# INOUT.net
KiCad netlist of a schematic drawn in Altium Designer
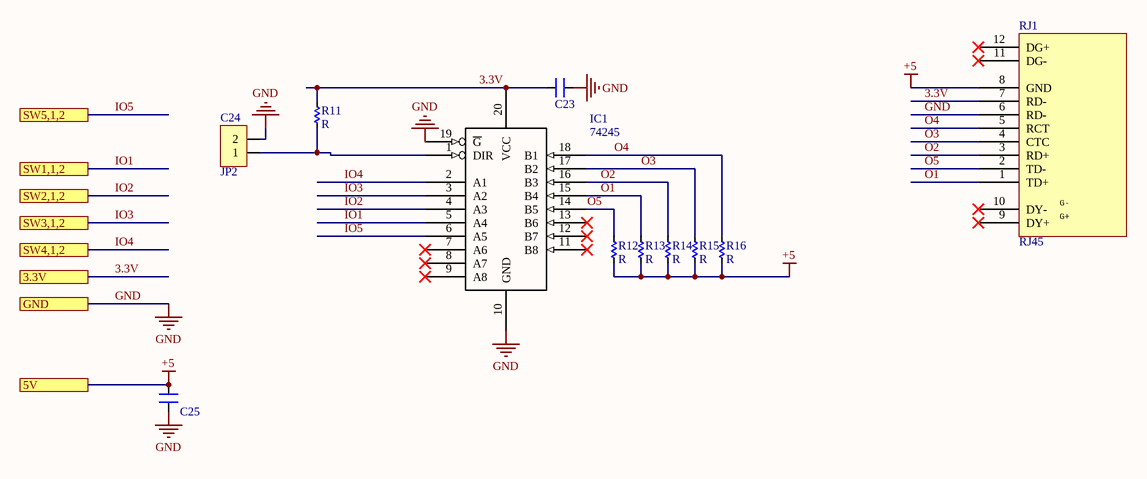
[diagram p0: INOUT.SchDoc]

(export (version "E")
  (design (tool "Eeschema 10.0.6"))
  (components
    (comp (ref "C23") (value "CN") (footprint "CN-SMD-0603_big") (libsource (lib "nhan") (part "CN")))
    (comp (ref "C24")
      (value "JP2")
      (footprint "JP2-CLOSED")
      (description "WR-PHD 2.54 mm Angled Socket Header")
      (fields
        (field (name "MANUFACTURER") "Würth Elektronik eiSos GmbH")
        (field (name "PARTNO") "613002143121")
        (field (name "CREATED BY") "Karrer Zheng")
      )
      (libsource (lib "nhan") (part "JP2"))
    )
    (comp (ref "C25") (value "CN") (footprint "CN-SMD-0603_big") (libsource (lib "nhan") (part "CN")))
    (comp (ref "IC1")
      (value "74245")
      (footprint "SO20")
      (description "Octal bus tranceiver; 3-state")
      (fields (field (name "COPYRIGHT BY") "VanDungEvn@gmail.com"))
      (libsource (lib "BanLinhKien") (part "74245"))
    )
    (comp (ref "R11") (value "R") (footprint "RES-SMD-0603_BIG") (libsource (lib "nhan") (part "R")))
    (comp (ref "R12") (value "R") (footprint "RES-SMD-0603_BIG") (libsource (lib "nhan") (part "R")))
    (comp (ref "R13") (value "R") (footprint "RES-SMD-0603_BIG") (libsource (lib "nhan") (part "R")))
    (comp (ref "R14") (value "R") (footprint "RES-SMD-0603_BIG") (libsource (lib "nhan") (part "R")))
    (comp (ref "R15") (value "R") (footprint "RES-SMD-0603_BIG") (libsource (lib "nhan") (part "R")))
    (comp (ref "R16") (value "R") (footprint "RES-SMD-0603_BIG") (libsource (lib "nhan") (part "R")))
    (comp (ref "RJ1") (value "RJ45") (footprint "RJ45-Dung") (libsource (lib "nhan") (part "CON JR45")))
  )
  (nets
    (net (code "1") (name "+5") (class "Default")
      (node (ref "C25") (pin "2") (pinfunction "2_2") (pintype "passive"))
      (node (ref "R12") (pin "2") (pinfunction "2_2") (pintype "passive"))
      (node (ref "R13") (pin "2") (pinfunction "2_2") (pintype "passive"))
      (node (ref "R14") (pin "2") (pinfunction "2_2") (pintype "passive"))
      (node (ref "R15") (pin "2") (pinfunction "2_2") (pintype "passive"))
      (node (ref "R16") (pin "2") (pinfunction "2_2") (pintype "passive"))
      (node (ref "RJ1") (pin "8") (pinfunction "GND_8") (pintype "power_in"))
    )
    (net (code "2") (name "/3.3V") (class "Default")
      (node (ref "C23") (pin "1") (pinfunction "1_1") (pintype "passive"))
      (node (ref "IC1") (pin "20") (pinfunction "VCC_20") (pintype "power_in"))
      (node (ref "R11") (pin "1") (pinfunction "1_1") (pintype "passive"))
      (node (ref "RJ1") (pin "7") (pinfunction "RD-_7") (pintype "passive"))
    )
    (net (code "3") (name "/IO1") (class "Default")
      (node (ref "IC1") (pin "5") (pinfunction "A4_5") (pintype "tri_state"))
    )
    (net (code "4") (name "/IO2") (class "Default")
      (node (ref "IC1") (pin "4") (pinfunction "A3_4") (pintype "tri_state"))
    )
    (net (code "5") (name "/IO3") (class "Default")
      (node (ref "IC1") (pin "3") (pinfunction "A2_3") (pintype "tri_state"))
    )
    (net (code "6") (name "/IO4") (class "Default")
      (node (ref "IC1") (pin "2") (pinfunction "A1_2") (pintype "tri_state"))
    )
    (net (code "7") (name "/IO5") (class "Default")
      (node (ref "IC1") (pin "6") (pinfunction "A5_6") (pintype "tri_state"))
    )
    (net (code "8") (name "/O1") (class "Default")
      (node (ref "IC1") (pin "15") (pinfunction "B4_15") (pintype "input"))
      (node (ref "R13") (pin "1") (pinfunction "1_1") (pintype "passive"))
      (node (ref "RJ1") (pin "1") (pinfunction "TD+_1") (pintype "passive"))
    )
    (net (code "9") (name "/O2") (class "Default")
      (node (ref "IC1") (pin "16") (pinfunction "B3_16") (pintype "input"))
      (node (ref "R14") (pin "1") (pinfunction "1_1") (pintype "passive"))
      (node (ref "RJ1") (pin "3") (pinfunction "RD+_3") (pintype "passive"))
    )
    (net (code "10") (name "/O3") (class "Default")
      (node (ref "IC1") (pin "17") (pinfunction "B2_17") (pintype "input"))
      (node (ref "R15") (pin "1") (pinfunction "1_1") (pintype "passive"))
      (node (ref "RJ1") (pin "4") (pinfunction "CTC_4") (pintype "passive"))
    )
    (net (code "11") (name "/O4") (class "Default")
      (node (ref "IC1") (pin "18") (pinfunction "B1_18") (pintype "input"))
      (node (ref "R16") (pin "1") (pinfunction "1_1") (pintype "passive"))
      (node (ref "RJ1") (pin "5") (pinfunction "RCT_5") (pintype "passive"))
    )
    (net (code "12") (name "/O5") (class "Default")
      (node (ref "IC1") (pin "14") (pinfunction "B5_14") (pintype "input"))
      (node (ref "R12") (pin "1") (pinfunction "1_1") (pintype "passive"))
      (node (ref "RJ1") (pin "2") (pinfunction "TD-_2") (pintype "passive"))
    )
    (net (code "13") (name "GND") (class "Default")
      (node (ref "C23") (pin "2") (pinfunction "2_2") (pintype "passive"))
      (node (ref "C24") (pin "2") (pinfunction "2_2") (pintype "passive"))
      (node (ref "C25") (pin "1") (pinfunction "1_1") (pintype "passive"))
      (node (ref "IC1") (pin "10") (pinfunction "GND_10") (pintype "power_in"))
      (node (ref "IC1") (pin "19") (pinfunction "~{G}_19") (pintype "input"))
      (node (ref "RJ1") (pin "6") (pinfunction "RD-_6") (pintype "passive"))
    )
    (net (code "14") (name "Net-(IC1-DIR)") (class "Default")
      (node (ref "C24") (pin "1") (pinfunction "1_1") (pintype "passive"))
      (node (ref "IC1") (pin "1") (pinfunction "DIR_1") (pintype "input"))
      (node (ref "R11") (pin "2") (pinfunction "2_2") (pintype "passive"))
    )
    (net (code "15") (name "unconnected-(IC1-A6-Pad7)") (class "Default")
      (node (ref "IC1") (pin "7") (pinfunction "A6_7") (pintype "tri_state+no_connect"))
    )
    (net (code "16") (name "unconnected-(IC1-A7-Pad8)") (class "Default")
      (node (ref "IC1") (pin "8") (pinfunction "A7_8") (pintype "tri_state+no_connect"))
    )
    (net (code "17") (name "unconnected-(IC1-A8-Pad9)") (class "Default")
      (node (ref "IC1") (pin "9") (pinfunction "A8_9") (pintype "tri_state+no_connect"))
    )
    (net (code "18") (name "unconnected-(IC1-B6-Pad13)") (class "Default")
      (node (ref "IC1") (pin "13") (pinfunction "B6_13") (pintype "input+no_connect"))
    )
    (net (code "19") (name "unconnected-(IC1-B7-Pad12)") (class "Default")
      (node (ref "IC1") (pin "12") (pinfunction "B7_12") (pintype "input+no_connect"))
    )
    (net (code "20") (name "unconnected-(IC1-B8-Pad11)") (class "Default")
      (node (ref "IC1") (pin "11") (pinfunction "B8_11") (pintype "input+no_connect"))
    )
    (net (code "21") (name "unconnected-(RJ1-DG+-Pad12)") (class "Default")
      (node (ref "RJ1") (pin "12") (pinfunction "DG+_12") (pintype "passive+no_connect"))
    )
    (net (code "22") (name "unconnected-(RJ1-DG--Pad11)") (class "Default")
      (node (ref "RJ1") (pin "11") (pinfunction "DG-_11") (pintype "passive+no_connect"))
    )
    (net (code "23") (name "unconnected-(RJ1-DY+-Pad9)") (class "Default")
      (node (ref "RJ1") (pin "9") (pinfunction "DY+_9") (pintype "passive+no_connect"))
    )
    (net (code "24") (name "unconnected-(RJ1-DY--Pad10)") (class "Default")
      (node (ref "RJ1") (pin "10") (pinfunction "DY-_10") (pintype "passive+no_connect"))
    )
  )
)
